# MCU-schematic.net
KiCad netlist of a schematic drawn in EAGLE
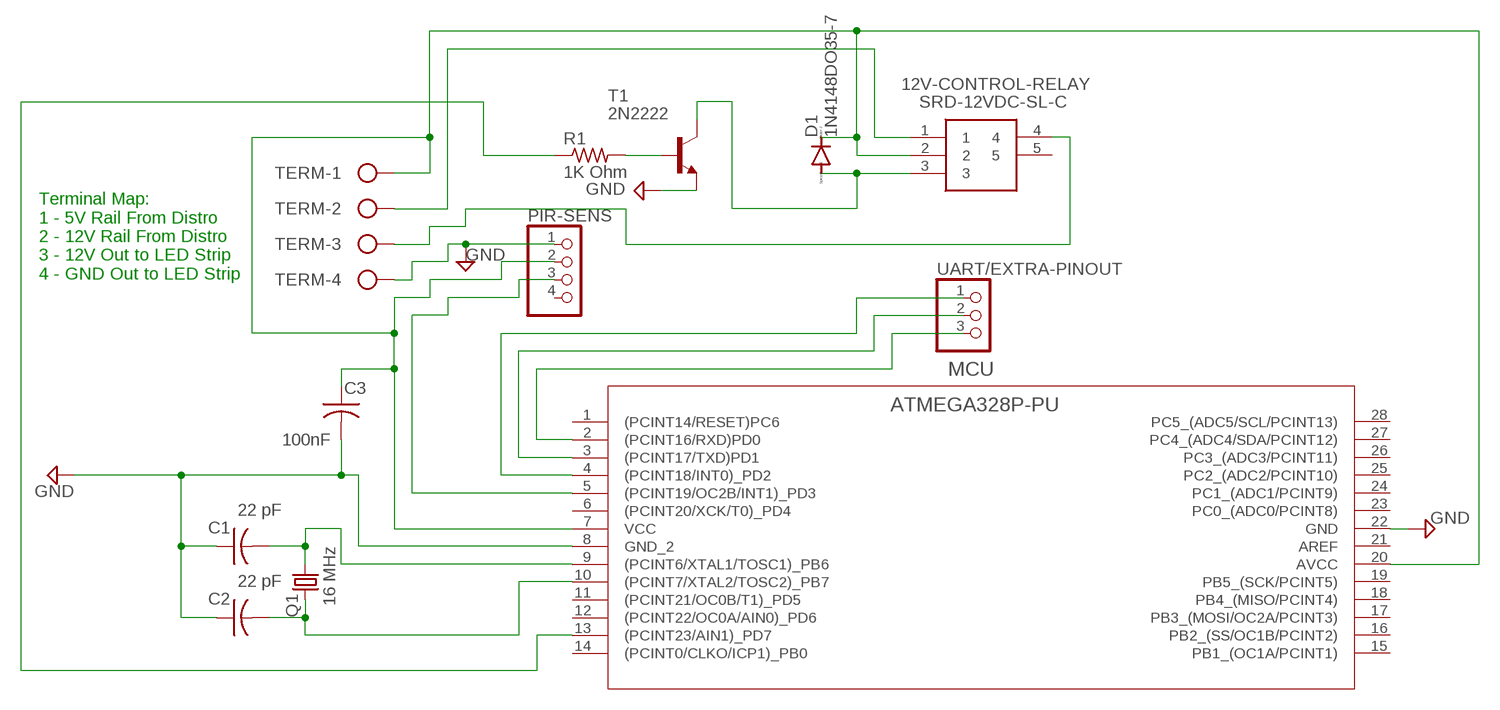
[diagram p0: schematic, sheet 1]

(export (version "E")
  (design (tool "Eeschema 10.0.6"))
  (components
    (comp (ref "12V-CONTROL-RELAY")
      (value "SRD-12VDC-SL-C")
      (footprint "eagle-import:SRD")
      (libsource (lib "eagle-import") (part "SRD-12VDC-SL-C"))
    )
    (comp (ref "C1")
      (value "22 pF")
      (footprint "eagle-import:C0805")
      (fields (field (name "MF") "SAMSUNG ELECTRO-MECHANICS") (field (name "MPN") "CL21C220JBANNNC"))
      (libsource (lib "eagle-import") (part "C-USC0805"))
    )
    (comp (ref "C2")
      (value "22 pF")
      (footprint "eagle-import:C0805")
      (fields (field (name "MF") "SAMSUNG ELECTRO-MECHANICS") (field (name "MPN") "CL21C220JBANNNC"))
      (libsource (lib "eagle-import") (part "C-USC0805"))
    )
    (comp (ref "C3")
      (value "100nF")
      (footprint "eagle-import:C0805")
      (fields (field (name "MF") "KEMET") (field (name "MPN") "C0805C104J5RACTU"))
      (libsource (lib "eagle-import") (part "C-USC0805"))
    )
    (comp (ref "D1")
      (value "1N4148DO35-7")
      (footprint "eagle-import:DO35-7")
      (libsource (lib "eagle-import") (part "1N4148DO35-7"))
    )
    (comp (ref "MCU")
      (value "ATMEGA328P-PU")
      (footprint "eagle-import:28P3_ATM")
      (fields
        (field (name "MF") "MICROCHIP")
        (field (name "COPYRIGHT") "Copyright (C) 2021 Ultra Librarian. All rights reserved.")
      )
      (libsource (lib "eagle-import") (part "ATMEGA328P-PU"))
    )
    (comp (ref "PIR-SENS")
      (value "PINHD-1X4")
      (footprint "eagle-import:1X04")
      (libsource (lib "eagle-import") (part "PINHD-1X4"))
    )
    (comp (ref "Q1")
      (value "16 MHz")
      (footprint "eagle-import:HC49_S")
      (libsource (lib "eagle-import") (part "CRYSTALHC49S"))
    )
    (comp (ref "R1")
      (value "1K Ohm")
      (footprint "eagle-import:R0805")
      (fields (field (name "MF") "TDK") (field (name "MPN") "MPZ2012S102JTD25"))
      (libsource (lib "eagle-import") (part "R-US_R0805"))
    )
    (comp (ref "T1")
      (value "2N2222")
      (footprint "eagle-import:TO18")
      (fields (field (name "MF") "MULTICOMP PRO"))
      (libsource (lib "eagle-import") (part "2N2222"))
    )
    (comp (ref "TERM")
      (value "W237-4")
      (footprint "eagle-import:W237-4")
      (libsource (lib "eagle-import") (part "W237-4"))
    )
    (comp (ref "UART/EXTRA-PINOUT")
      (value "PINHD-1X3")
      (footprint "eagle-import:1X03")
      (libsource (lib "eagle-import") (part "PINHD-1X3"))
    )
  )
  (nets
    (net (code "1") (name "GND") (class "Default")
      (node (ref "C1") (pin "1") (pinfunction "1_1") (pintype "passive"))
      (node (ref "C2") (pin "1") (pinfunction "1_1") (pintype "passive"))
      (node (ref "C3") (pin "2") (pinfunction "2_2") (pintype "passive"))
      (node (ref "MCU") (pin "22") (pinfunction "GND_22") (pintype "power_in"))
      (node (ref "MCU") (pin "8") (pinfunction "GND_2_8") (pintype "power_in"))
      (node (ref "PIR-SENS") (pin "1") (pinfunction "1_1") (pintype "passive"))
      (node (ref "T1") (pin "1") (pinfunction "E_1") (pintype "passive"))
      (node (ref "TERM") (pin "4") (pinfunction "KL_4") (pintype "passive"))
    )
    (net (code "2") (name "Net-(MCU-(PCINT6{slash}XTAL1{slash}TOSC1)_PB6)") (class "Default")
      (node (ref "C1") (pin "2") (pinfunction "2_2") (pintype "passive"))
      (node (ref "MCU") (pin "9") (pinfunction "(PCINT6/XTAL1/TOSC1)_PB6_9") (pintype "bidirectional"))
      (node (ref "Q1") (pin "2") (pinfunction "2_2") (pintype "passive"))
    )
    (net (code "3") (name "Net-(MCU-(PCINT7{slash}XTAL2{slash}TOSC2)_PB7)") (class "Default")
      (node (ref "C2") (pin "2") (pinfunction "2_2") (pintype "passive"))
      (node (ref "MCU") (pin "10") (pinfunction "(PCINT7/XTAL2/TOSC2)_PB7_10") (pintype "bidirectional"))
      (node (ref "Q1") (pin "1") (pinfunction "1_1") (pintype "passive"))
    )
    (net (code "4") (name "Net-(MCU-(PCINT16{slash}RXD)PD0)") (class "Default")
      (node (ref "MCU") (pin "2") (pinfunction "(PCINT16/RXD)PD0_2") (pintype "bidirectional"))
      (node (ref "UART/EXTRA-PINOUT") (pin "3") (pinfunction "3_3") (pintype "passive"))
    )
    (net (code "5") (name "Net-(MCU-(PCINT17{slash}TXD)PD1)") (class "Default")
      (node (ref "MCU") (pin "3") (pinfunction "(PCINT17/TXD)PD1_3") (pintype "bidirectional"))
      (node (ref "UART/EXTRA-PINOUT") (pin "2") (pinfunction "2_2") (pintype "passive"))
    )
    (net (code "6") (name "Net-(MCU-(PCINT18{slash}INT0)_PD2)") (class "Default")
      (node (ref "MCU") (pin "4") (pinfunction "(PCINT18/INT0)_PD2_4") (pintype "bidirectional"))
      (node (ref "UART/EXTRA-PINOUT") (pin "1") (pinfunction "1_1") (pintype "passive"))
    )
    (net (code "7") (name "Net-(MCU-(PCINT19{slash}OC2B{slash}INT1)_PD3)") (class "Default")
      (node (ref "MCU") (pin "5") (pinfunction "(PCINT19/OC2B/INT1)_PD3_5") (pintype "bidirectional"))
      (node (ref "PIR-SENS") (pin "3") (pinfunction "3_3") (pintype "passive"))
    )
    (net (code "8") (name "Net-(MCU-(PCINT23{slash}AIN1)_PD7)") (class "Default")
      (node (ref "MCU") (pin "13") (pinfunction "(PCINT23/AIN1)_PD7_13") (pintype "bidirectional"))
      (node (ref "R1") (pin "1") (pinfunction "1_1") (pintype "passive"))
    )
    (net (code "9") (name "Net-(MCU-AVCC)") (class "Default")
      (node (ref "12V-CONTROL-RELAY") (pin "2") (pinfunction "2_2") (pintype "bidirectional"))
      (node (ref "C3") (pin "1") (pinfunction "1_1") (pintype "passive"))
      (node (ref "D1") (pin "C") (pinfunction "C_C") (pintype "passive"))
      (node (ref "MCU") (pin "20") (pinfunction "AVCC_20") (pintype "power_in"))
      (node (ref "MCU") (pin "7") (pinfunction "VCC_7") (pintype "power_in"))
      (node (ref "PIR-SENS") (pin "2") (pinfunction "2_2") (pintype "passive"))
      (node (ref "TERM") (pin "1") (pinfunction "KL_1") (pintype "passive"))
    )
    (net (code "10") (name "Net-(T1-B)") (class "Default")
      (node (ref "R1") (pin "2") (pinfunction "2_2") (pintype "passive"))
      (node (ref "T1") (pin "2") (pinfunction "B_2") (pintype "passive"))
    )
    (net (code "11") (name "Net-(T1-C)") (class "Default")
      (node (ref "12V-CONTROL-RELAY") (pin "3") (pinfunction "3_3") (pintype "bidirectional"))
      (node (ref "D1") (pin "A") (pinfunction "A_A") (pintype "passive"))
      (node (ref "T1") (pin "3") (pinfunction "C_3") (pintype "passive"))
    )
    (net (code "12") (name "Net-(TERMB-KL)") (class "Default")
      (node (ref "12V-CONTROL-RELAY") (pin "1") (pinfunction "1_1") (pintype "bidirectional"))
      (node (ref "TERM") (pin "2") (pinfunction "KL_2") (pintype "passive"))
    )
    (net (code "13") (name "Net-(TERMC-KL)") (class "Default")
      (node (ref "12V-CONTROL-RELAY") (pin "4") (pinfunction "4_4") (pintype "bidirectional"))
      (node (ref "TERM") (pin "3") (pinfunction "KL_3") (pintype "passive"))
    )
    (net (code "14") (name "unconnected-(12V-CONTROL-RELAY-Pad5)") (class "Default")
      (node (ref "12V-CONTROL-RELAY") (pin "5") (pinfunction "5_5") (pintype "bidirectional"))
    )
    (net (code "15") (name "unconnected-(MCU-(PCINT0{slash}CLKO{slash}ICP1)_PB0-Pad14)") (class "Default")
      (node (ref "MCU") (pin "14") (pinfunction "(PCINT0/CLKO/ICP1)_PB0_14") (pintype "bidirectional"))
    )
    (net (code "16") (name "unconnected-(MCU-(PCINT14{slash}RESET)PC6-Pad1)") (class "Default")
      (node (ref "MCU") (pin "1") (pinfunction "(PCINT14/RESET)PC6_1") (pintype "bidirectional"))
    )
    (net (code "17") (name "unconnected-(MCU-(PCINT20{slash}XCK{slash}T0)_PD4-Pad6)") (class "Default")
      (node (ref "MCU") (pin "6") (pinfunction "(PCINT20/XCK/T0)_PD4_6") (pintype "bidirectional"))
    )
    (net (code "18") (name "unconnected-(MCU-(PCINT21{slash}OC0B{slash}T1)_PD5-Pad11)") (class "Default")
      (node (ref "MCU") (pin "11") (pinfunction "(PCINT21/OC0B/T1)_PD5_11") (pintype "bidirectional"))
    )
    (net (code "19") (name "unconnected-(MCU-(PCINT22{slash}OC0A{slash}AIN0)_PD6-Pad12)") (class "Default")
      (node (ref "MCU") (pin "12") (pinfunction "(PCINT22/OC0A/AIN0)_PD6_12") (pintype "bidirectional"))
    )
    (net (code "20") (name "unconnected-(MCU-AREF-Pad21)") (class "Default")
      (node (ref "MCU") (pin "21") (pinfunction "AREF_21") (pintype "passive"))
    )
    (net (code "21") (name "unconnected-(MCU-PB1_(OC1A{slash}PCINT1)-Pad15)") (class "Default")
      (node (ref "MCU") (pin "15") (pinfunction "PB1_(OC1A/PCINT1)_15") (pintype "bidirectional"))
    )
    (net (code "22") (name "unconnected-(MCU-PB2_(SS{slash}OC1B{slash}PCINT2)-Pad16)") (class "Default")
      (node (ref "MCU") (pin "16") (pinfunction "PB2_(SS/OC1B/PCINT2)_16") (pintype "bidirectional"))
    )
    (net (code "23") (name "unconnected-(MCU-PB3_(MOSI{slash}OC2A{slash}PCINT3)-Pad17)") (class "Default")
      (node (ref "MCU") (pin "17") (pinfunction "PB3_(MOSI/OC2A/PCINT3)_17") (pintype "bidirectional"))
    )
    (net (code "24") (name "unconnected-(MCU-PB4_(MISO{slash}PCINT4)-Pad18)") (class "Default")
      (node (ref "MCU") (pin "18") (pinfunction "PB4_(MISO/PCINT4)_18") (pintype "bidirectional"))
    )
    (net (code "25") (name "unconnected-(MCU-PB5_(SCK{slash}PCINT5)-Pad19)") (class "Default")
      (node (ref "MCU") (pin "19") (pinfunction "PB5_(SCK/PCINT5)_19") (pintype "bidirectional"))
    )
    (net (code "26") (name "unconnected-(MCU-PC0_(ADC0{slash}PCINT8)-Pad23)") (class "Default")
      (node (ref "MCU") (pin "23") (pinfunction "PC0_(ADC0/PCINT8)_23") (pintype "bidirectional"))
    )
    (net (code "27") (name "unconnected-(MCU-PC1_(ADC1{slash}PCINT9)-Pad24)") (class "Default")
      (node (ref "MCU") (pin "24") (pinfunction "PC1_(ADC1/PCINT9)_24") (pintype "bidirectional"))
    )
    (net (code "28") (name "unconnected-(MCU-PC2_(ADC2{slash}PCINT10)-Pad25)") (class "Default")
      (node (ref "MCU") (pin "25") (pinfunction "PC2_(ADC2/PCINT10)_25") (pintype "bidirectional"))
    )
    (net (code "29") (name "unconnected-(MCU-PC3_(ADC3{slash}PCINT11)-Pad26)") (class "Default")
      (node (ref "MCU") (pin "26") (pinfunction "PC3_(ADC3/PCINT11)_26") (pintype "bidirectional"))
    )
    (net (code "30") (name "unconnected-(MCU-PC4_(ADC4{slash}SDA{slash}PCINT12)-Pad27)") (class "Default")
      (node (ref "MCU") (pin "27") (pinfunction "PC4_(ADC4/SDA/PCINT12)_27") (pintype "bidirectional"))
    )
    (net (code "31") (name "unconnected-(MCU-PC5_(ADC5{slash}SCL{slash}PCINT13)-Pad28)") (class "Default")
      (node (ref "MCU") (pin "28") (pinfunction "PC5_(ADC5/SCL/PCINT13)_28") (pintype "bidirectional"))
    )
    (net (code "32") (name "unconnected-(PIR-SENS-Pad4)") (class "Default")
      (node (ref "PIR-SENS") (pin "4") (pinfunction "4_4") (pintype "passive"))
    )
  )
)
